# AnalogOutputs.net
KiCad netlist of a schematic drawn in Altium Designer
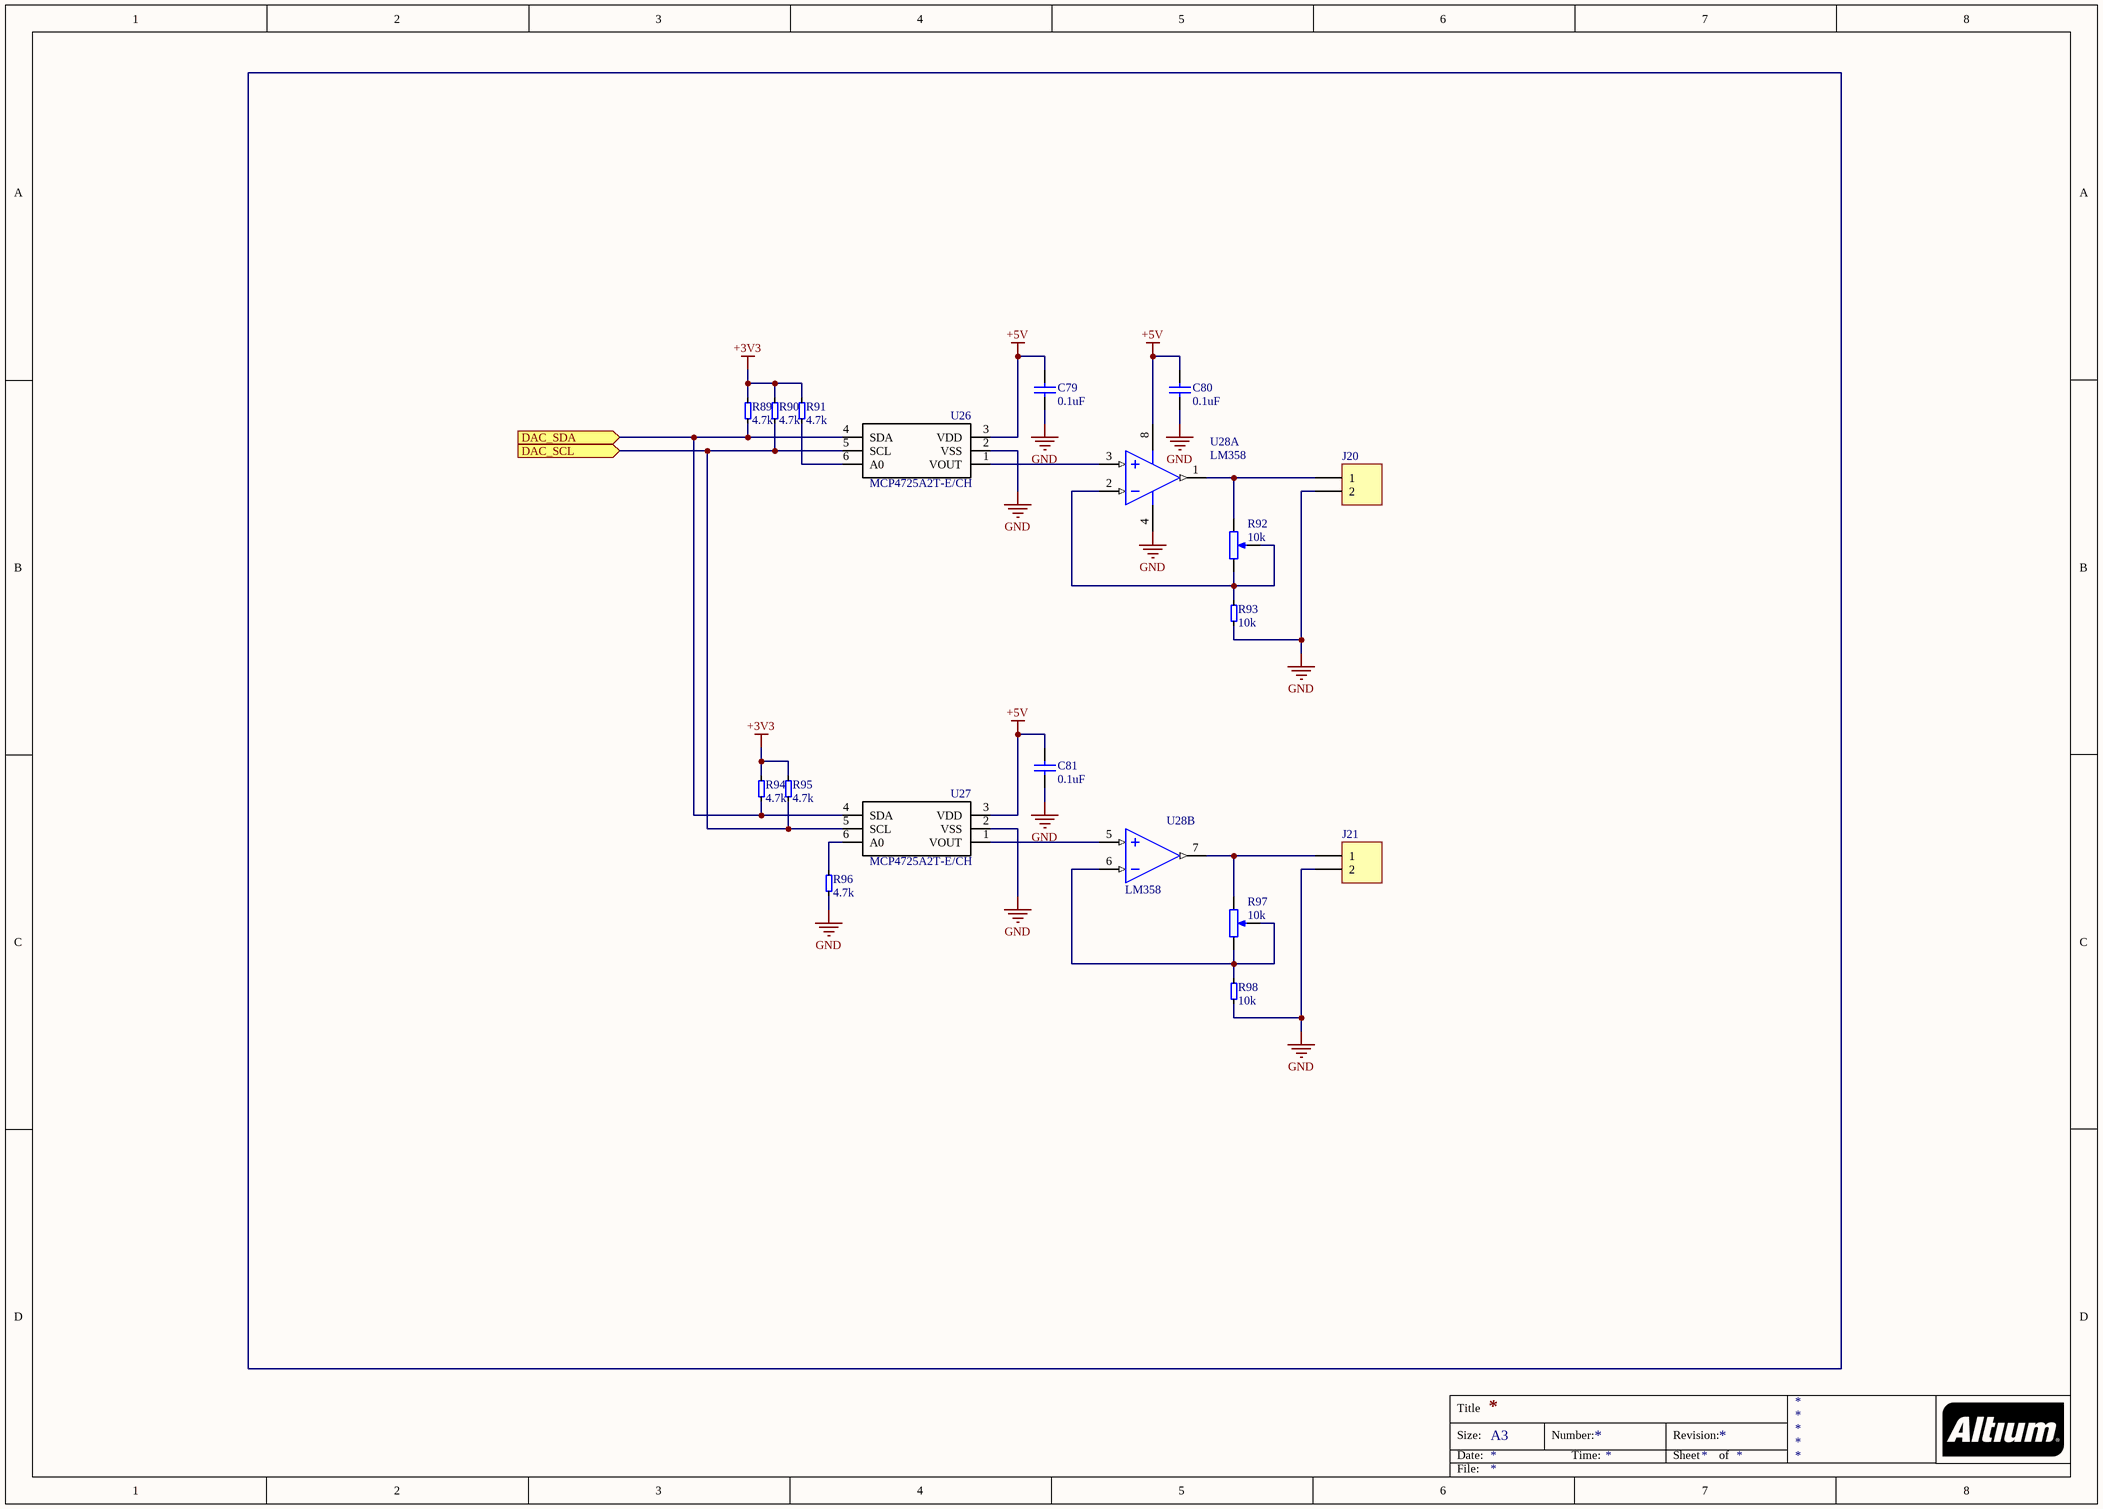
[diagram p0: AnalogOutputs.SchDoc]

(export (version "E")
  (design (tool "Eeschema 10.0.6"))
  (components
    (comp (ref "C79")
      (value "0.1uF")
      (footprint "C_ceramic_0603")
      (description "CAP CER 0.1UF 50V X7R 0603")
      (fields
        (field (name "MANUFACTURER") "Yageo")
        (field (name "MANUFACTURER PART NUMBER") "CC0603KPX7R9BB104")
      )
      (libsource (lib "Miscellaneous Devices") (part "Cap"))
    )
    (comp (ref "C80")
      (value "0.1uF")
      (footprint "C_ceramic_0603")
      (description "CAP CER 0.1UF 50V X7R 0603")
      (fields
        (field (name "MANUFACTURER") "Yageo")
        (field (name "MANUFACTURER PART NUMBER") "CC0603KPX7R9BB104")
      )
      (libsource (lib "Miscellaneous Devices") (part "Cap"))
    )
    (comp (ref "C81")
      (value "0.1uF")
      (footprint "C_ceramic_0603")
      (description "CAP CER 0.1UF 50V X7R 0603")
      (fields
        (field (name "MANUFACTURER") "Yageo")
        (field (name "MANUFACTURER PART NUMBER") "CC0603KPX7R9BB104")
      )
      (libsource (lib "Miscellaneous Devices") (part "Cap"))
    )
    (comp (ref "J20")
      (value "CIM025P5")
      (footprint "HDR1X2")
      (description "TERM BLK 2P SIDE ENT 5.08MM PCB")
      (fields (field (name "MANUFACTURER") "Sauro"))
      (libsource (lib "Miscellaneous Connectors") (part "Header 2"))
    )
    (comp (ref "J21")
      (value "CIM025P5")
      (footprint "HDR1X2")
      (description "TERM BLK 2P SIDE ENT 5.08MM PCB")
      (fields (field (name "MANUFACTURER") "Sauro"))
      (libsource (lib "Miscellaneous Connectors") (part "Header 2"))
    )
    (comp (ref "R89")
      (value "4.7k")
      (footprint "R_0603")
      (description "RES SMD 80.6K OHM 1% 1/10W 0603")
      (fields
        (field (name "MANUFACTURER") "Yageo")
        (field (name "MANUFACTURER PART NUMBER") "RC0603FR-0780K6L")
      )
      (libsource (lib "LED_LIB") (part "R_0402"))
    )
    (comp (ref "R90")
      (value "4.7k")
      (footprint "R_0603")
      (description "RES SMD 80.6K OHM 1% 1/10W 0603")
      (fields
        (field (name "MANUFACTURER") "Yageo")
        (field (name "MANUFACTURER PART NUMBER") "RC0603FR-0780K6L")
      )
      (libsource (lib "LED_LIB") (part "R_0402"))
    )
    (comp (ref "R91")
      (value "4.7k")
      (footprint "R_0603")
      (description "RES SMD 80.6K OHM 1% 1/10W 0603")
      (fields
        (field (name "MANUFACTURER") "Yageo")
        (field (name "MANUFACTURER PART NUMBER") "RC0603FR-0780K6L")
      )
      (libsource (lib "LED_LIB") (part "R_0402"))
    )
    (comp (ref "R92")
      (value "10k")
      (footprint "ST4EA_Trimmer")
      (description "Potentiometer")
      (fields (field (name "PUBLISHER") "Altium Limited"))
      (libsource (lib "SchLib") (part "RPot"))
    )
    (comp (ref "R93")
      (value "10k")
      (footprint "R_0603")
      (description "RES SMD 80.6K OHM 1% 1/10W 0603")
      (fields
        (field (name "MANUFACTURER") "Yageo")
        (field (name "MANUFACTURER PART NUMBER") "RC0603FR-0780K6L")
      )
      (libsource (lib "LED_LIB") (part "R_0402"))
    )
    (comp (ref "R94")
      (value "4.7k")
      (footprint "R_0603")
      (description "RES SMD 80.6K OHM 1% 1/10W 0603")
      (fields
        (field (name "MANUFACTURER") "Yageo")
        (field (name "MANUFACTURER PART NUMBER") "RC0603FR-0780K6L")
      )
      (libsource (lib "LED_LIB") (part "R_0402"))
    )
    (comp (ref "R95")
      (value "4.7k")
      (footprint "R_0603")
      (description "RES SMD 80.6K OHM 1% 1/10W 0603")
      (fields
        (field (name "MANUFACTURER") "Yageo")
        (field (name "MANUFACTURER PART NUMBER") "RC0603FR-0780K6L")
      )
      (libsource (lib "LED_LIB") (part "R_0402"))
    )
    (comp (ref "R96")
      (value "4.7k")
      (footprint "R_0603")
      (description "RES SMD 80.6K OHM 1% 1/10W 0603")
      (fields
        (field (name "MANUFACTURER") "Yageo")
        (field (name "MANUFACTURER PART NUMBER") "RC0603FR-0780K6L")
      )
      (libsource (lib "LED_LIB") (part "R_0402"))
    )
    (comp (ref "R97")
      (value "10k")
      (footprint "ST4EA_Trimmer")
      (description "Potentiometer")
      (fields (field (name "PUBLISHER") "Altium Limited"))
      (libsource (lib "SchLib") (part "RPot"))
    )
    (comp (ref "R98")
      (value "10k")
      (footprint "R_0603")
      (description "RES SMD 80.6K OHM 1% 1/10W 0603")
      (fields
        (field (name "MANUFACTURER") "Yageo")
        (field (name "MANUFACTURER PART NUMBER") "RC0603FR-0780K6L")
      )
      (libsource (lib "LED_LIB") (part "R_0402"))
    )
    (comp (ref "U26")
      (value "MCP4725A2T-E/CH")
      (footprint "SOT-23-6_MC")
      (description "12 Bit Digital to Analog Converter 1 SOT-23-6")
      (fields (field (name "MF") "Microchip"))
      (libsource (lib "4ADI_2DO") (part "MCP4725A2T-E/CH"))
    )
    (comp (ref "U27")
      (value "MCP4725A2T-E/CH")
      (footprint "SOT-23-6_MC")
      (description "12 Bit Digital to Analog Converter 1 SOT-23-6")
      (fields (field (name "MF") "Microchip"))
      (libsource (lib "4ADI_2DO") (part "MCP4725A2T-E/CH"))
    )
    (comp (ref "U28")
      (value "LM358")
      (footprint "SOIC-8 - 3.9mm Body")
      (description "Linear Operational Amplifier")
      (fields (field (name "PUBLISHER") "Altium Limited"))
      (libsource (lib "4ADI_2DO") (part "Op Amp"))
    )
  )
  (nets
    (net (code "1") (name "+3V3") (class "Default")
      (node (ref "R89") (pin "1") (pinfunction "1_1") (pintype "passive"))
      (node (ref "R90") (pin "1") (pinfunction "1_1") (pintype "passive"))
      (node (ref "R91") (pin "1") (pinfunction "1_1") (pintype "passive"))
      (node (ref "R94") (pin "1") (pinfunction "1_1") (pintype "passive"))
      (node (ref "R95") (pin "1") (pinfunction "1_1") (pintype "passive"))
    )
    (net (code "2") (name "+5V") (class "Default")
      (node (ref "C79") (pin "2") (pinfunction "2_2") (pintype "passive"))
      (node (ref "C80") (pin "2") (pinfunction "2_2") (pintype "passive"))
      (node (ref "C81") (pin "2") (pinfunction "2_2") (pintype "passive"))
      (node (ref "U26") (pin "3") (pinfunction "VDD_3") (pintype "passive"))
      (node (ref "U27") (pin "3") (pinfunction "VDD_3") (pintype "passive"))
      (node (ref "U28") (pin "8") (pinfunction "V+_8") (pintype "power_in"))
    )
    (net (code "3") (name "/DAC_SCL") (class "Default")
      (node (ref "R90") (pin "2") (pinfunction "2_2") (pintype "passive"))
      (node (ref "R95") (pin "2") (pinfunction "2_2") (pintype "passive"))
      (node (ref "U26") (pin "5") (pinfunction "SCL_5") (pintype "passive"))
      (node (ref "U27") (pin "5") (pinfunction "SCL_5") (pintype "passive"))
    )
    (net (code "4") (name "/DAC_SDA") (class "Default")
      (node (ref "R89") (pin "2") (pinfunction "2_2") (pintype "passive"))
      (node (ref "R94") (pin "2") (pinfunction "2_2") (pintype "passive"))
      (node (ref "U26") (pin "4") (pinfunction "SDA_4") (pintype "passive"))
      (node (ref "U27") (pin "4") (pinfunction "SDA_4") (pintype "passive"))
    )
    (net (code "5") (name "GND") (class "Default")
      (node (ref "C79") (pin "1") (pinfunction "1_1") (pintype "passive"))
      (node (ref "C80") (pin "1") (pinfunction "1_1") (pintype "passive"))
      (node (ref "C81") (pin "1") (pinfunction "1_1") (pintype "passive"))
      (node (ref "J20") (pin "2") (pinfunction "2_2") (pintype "passive"))
      (node (ref "J21") (pin "2") (pinfunction "2_2") (pintype "passive"))
      (node (ref "R93") (pin "2") (pinfunction "2_2") (pintype "passive"))
      (node (ref "R96") (pin "2") (pinfunction "2_2") (pintype "passive"))
      (node (ref "R98") (pin "2") (pinfunction "2_2") (pintype "passive"))
      (node (ref "U26") (pin "2") (pinfunction "VSS_2") (pintype "passive"))
      (node (ref "U27") (pin "2") (pinfunction "VSS_2") (pintype "passive"))
      (node (ref "U28") (pin "4") (pinfunction "GND_4") (pintype "power_in"))
    )
    (net (code "6") (name "Net-(R92-BOT)") (class "Default")
      (node (ref "R92") (pin "2") (pinfunction "BOT_2") (pintype "passive"))
      (node (ref "R92") (pin "3") (pinfunction "TAP_3") (pintype "passive"))
      (node (ref "R93") (pin "1") (pinfunction "1_1") (pintype "passive"))
      (node (ref "U28") (pin "2") (pinfunction "IN_A-_2") (pintype "input"))
    )
    (net (code "7") (name "Net-(R92-TOP)") (class "Default")
      (node (ref "J20") (pin "1") (pinfunction "1_1") (pintype "passive"))
      (node (ref "R92") (pin "1") (pinfunction "TOP_1") (pintype "passive"))
      (node (ref "U28") (pin "1") (pinfunction "OUT_A_1") (pintype "output"))
    )
    (net (code "8") (name "Net-(R97-BOT)") (class "Default")
      (node (ref "R97") (pin "2") (pinfunction "BOT_2") (pintype "passive"))
      (node (ref "R97") (pin "3") (pinfunction "TAP_3") (pintype "passive"))
      (node (ref "R98") (pin "1") (pinfunction "1_1") (pintype "passive"))
      (node (ref "U28") (pin "6") (pinfunction "IN_B-_6") (pintype "input"))
    )
    (net (code "9") (name "Net-(R97-TOP)") (class "Default")
      (node (ref "J21") (pin "1") (pinfunction "1_1") (pintype "passive"))
      (node (ref "R97") (pin "1") (pinfunction "TOP_1") (pintype "passive"))
      (node (ref "U28") (pin "7") (pinfunction "OUT_B_7") (pintype "output"))
    )
    (net (code "10") (name "Net-(U26-A0)") (class "Default")
      (node (ref "R91") (pin "2") (pinfunction "2_2") (pintype "passive"))
      (node (ref "U26") (pin "6") (pinfunction "A0_6") (pintype "passive"))
    )
    (net (code "11") (name "Net-(U26-VOUT)") (class "Default")
      (node (ref "U26") (pin "1") (pinfunction "VOUT_1") (pintype "passive"))
      (node (ref "U28") (pin "3") (pinfunction "IN_A+_3") (pintype "input"))
    )
    (net (code "12") (name "Net-(U27-A0)") (class "Default")
      (node (ref "R96") (pin "1") (pinfunction "1_1") (pintype "passive"))
      (node (ref "U27") (pin "6") (pinfunction "A0_6") (pintype "passive"))
    )
    (net (code "13") (name "Net-(U27-VOUT)") (class "Default")
      (node (ref "U27") (pin "1") (pinfunction "VOUT_1") (pintype "passive"))
      (node (ref "U28") (pin "5") (pinfunction "IN_B+_5") (pintype "input"))
    )
  )
)
